# H-bridge.net
KiCad netlist of a schematic drawn in EAGLE
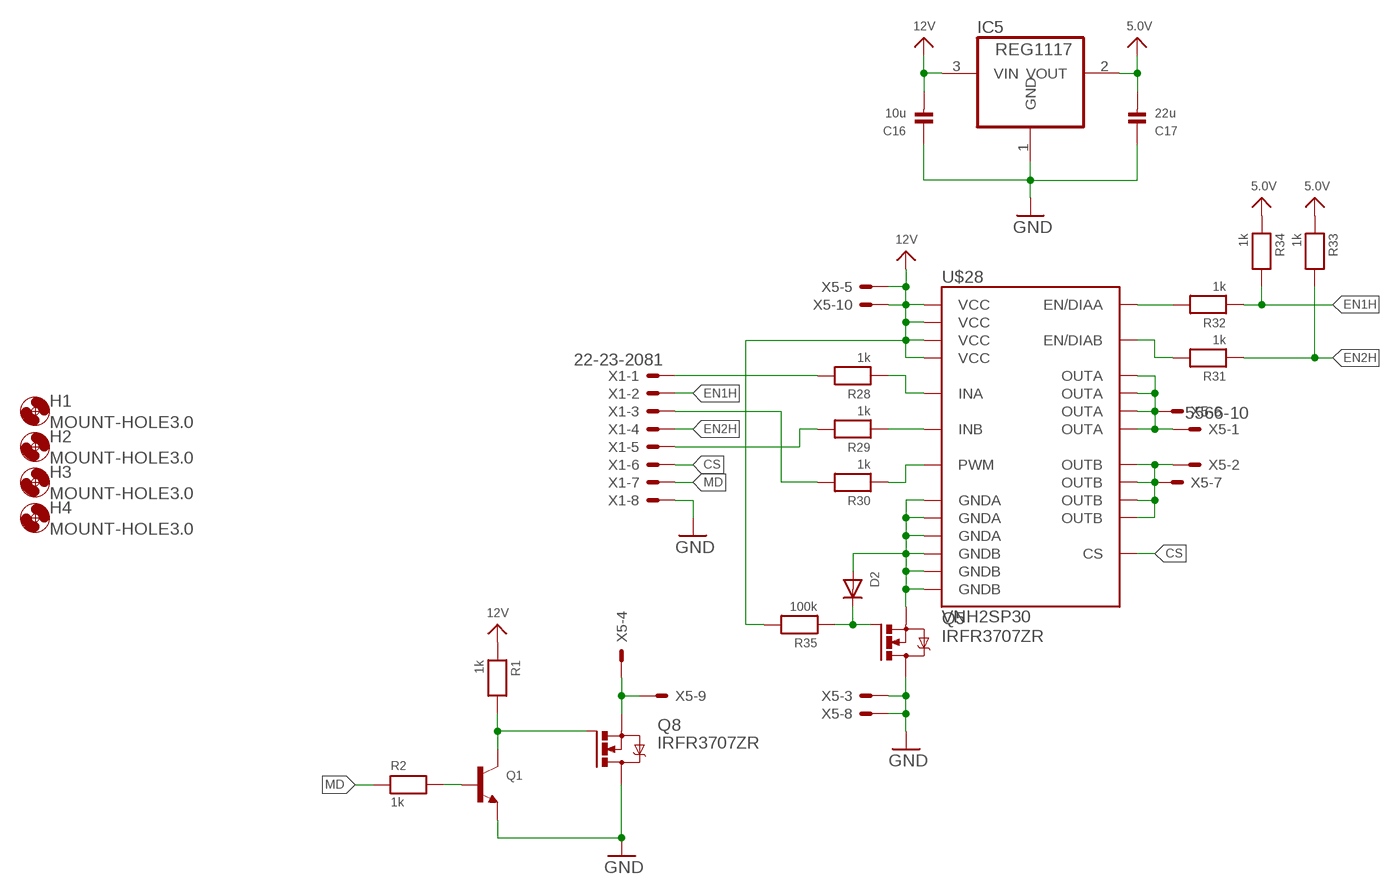
[diagram p0: schematic, sheet 1]

(export (version "E")
  (design (tool "Eeschema 10.0.6"))
  (components
    (comp (ref "C16")
      (value "10u")
      (footprint "eagle-import:_0805")
      (libsource (lib "eagle-import") (part "CAP_CERAMIC_0805"))
    )
    (comp (ref "C17")
      (value "22u")
      (footprint "eagle-import:_0805")
      (libsource (lib "eagle-import") (part "CAP_CERAMIC_0805"))
    )
    (comp (ref "D2")
      (value "DIODESMA")
      (footprint "eagle-import:SMADIODE")
      (libsource (lib "eagle-import") (part "DIODESMA"))
    )
    (comp (ref "H1")
      (value "MOUNT-HOLE3.0")
      (footprint "eagle-import:3,0")
      (libsource (lib "eagle-import") (part "MOUNT-HOLE3.0"))
    )
    (comp (ref "H2")
      (value "MOUNT-HOLE3.0")
      (footprint "eagle-import:3,0")
      (libsource (lib "eagle-import") (part "MOUNT-HOLE3.0"))
    )
    (comp (ref "H3")
      (value "MOUNT-HOLE3.0")
      (footprint "eagle-import:3,0")
      (libsource (lib "eagle-import") (part "MOUNT-HOLE3.0"))
    )
    (comp (ref "H4")
      (value "MOUNT-HOLE3.0")
      (footprint "eagle-import:3,0")
      (libsource (lib "eagle-import") (part "MOUNT-HOLE3.0"))
    )
    (comp (ref "IC5")
      (value "REG1117")
      (footprint "eagle-import:SOT223")
      (libsource (lib "eagle-import") (part "REG1117"))
    )
    (comp (ref "Q1")
      (value "TRANSISTOR_NPNWIDE")
      (footprint "eagle-import:SOT23-WIDE")
      (libsource (lib "eagle-import") (part "TRANSISTOR_NPNWIDE"))
    )
    (comp (ref "Q5")
      (value "IRFR3707ZR")
      (footprint "eagle-import:D-PAK_TO252AA")
      (libsource (lib "eagle-import") (part "IRFR3707ZR"))
    )
    (comp (ref "Q8")
      (value "IRFR3707ZR")
      (footprint "eagle-import:D-PAK_TO252AA")
      (libsource (lib "eagle-import") (part "IRFR3707ZR"))
    )
    (comp (ref "R1")
      (value "1k")
      (footprint "eagle-import:_0603")
      (libsource (lib "eagle-import") (part "RESISTOR_0603"))
    )
    (comp (ref "R2")
      (value "1k")
      (footprint "eagle-import:_0603")
      (libsource (lib "eagle-import") (part "RESISTOR_0603"))
    )
    (comp (ref "R28")
      (value "1k")
      (footprint "eagle-import:_0603")
      (libsource (lib "eagle-import") (part "RESISTOR_0603"))
    )
    (comp (ref "R29")
      (value "1k")
      (footprint "eagle-import:_0603")
      (libsource (lib "eagle-import") (part "RESISTOR_0603"))
    )
    (comp (ref "R30")
      (value "1k")
      (footprint "eagle-import:_0603")
      (libsource (lib "eagle-import") (part "RESISTOR_0603"))
    )
    (comp (ref "R31")
      (value "1k")
      (footprint "eagle-import:_0603")
      (libsource (lib "eagle-import") (part "RESISTOR_0603"))
    )
    (comp (ref "R32")
      (value "1k")
      (footprint "eagle-import:_0603")
      (libsource (lib "eagle-import") (part "RESISTOR_0603"))
    )
    (comp (ref "R33")
      (value "1k")
      (footprint "eagle-import:_0603")
      (libsource (lib "eagle-import") (part "RESISTOR_0603"))
    )
    (comp (ref "R34")
      (value "1k")
      (footprint "eagle-import:_0603")
      (libsource (lib "eagle-import") (part "RESISTOR_0603"))
    )
    (comp (ref "R35")
      (value "100k")
      (footprint "eagle-import:_0603")
      (libsource (lib "eagle-import") (part "RESISTOR_0603"))
    )
    (comp (ref "U$28")
      (value "VNH2SP30")
      (footprint "eagle-import:VNH2SP30")
      (libsource (lib "eagle-import") (part "VNH2SP30"))
    )
    (comp (ref "X1")
      (value "22-23-2081")
      (footprint "eagle-import:22-23-2081")
      (fields (field (name "MF") "MOLEX"))
      (libsource (lib "eagle-import") (part "22-23-2081"))
    )
    (comp (ref "X5")
      (value "5566-10")
      (footprint "eagle-import:5566-10")
      (libsource (lib "eagle-import") (part "5566-10"))
    )
  )
  (nets
    (net (code "1") (name "5.0V") (class "Default")
      (node (ref "C17") (pin "2") (pinfunction "P$2_2") (pintype "passive"))
      (node (ref "IC5") (pin "2") (pinfunction "VOUT_2") (pintype "output"))
      (node (ref "R33") (pin "1") (pinfunction "1_1") (pintype "passive"))
      (node (ref "R34") (pin "1") (pinfunction "1_1") (pintype "passive"))
    )
    (net (code "2") (name "12V") (class "Default")
      (node (ref "C16") (pin "2") (pinfunction "P$2_2") (pintype "passive"))
      (node (ref "IC5") (pin "3") (pinfunction "VIN_3") (pintype "input"))
      (node (ref "R1") (pin "1") (pinfunction "1_1") (pintype "passive"))
      (node (ref "R35") (pin "2") (pinfunction "2_2") (pintype "passive"))
      (node (ref "U$28") (pin "13") (pinfunction "VCC_13") (pintype "bidirectional"))
      (node (ref "U$28") (pin "23") (pinfunction "VCC_23") (pintype "bidirectional"))
      (node (ref "U$28") (pin "3") (pinfunction "VCC_3") (pintype "bidirectional"))
      (node (ref "U$28") (pin "SLUG1") (pinfunction "VCC_SLUG1") (pintype "bidirectional"))
      (node (ref "X5") (pin "10") (pinfunction "S_10") (pintype "passive"))
      (node (ref "X5") (pin "5") (pinfunction "S_5") (pintype "passive"))
    )
    (net (code "3") (name "CS") (class "Default")
      (node (ref "U$28") (pin "9") (pinfunction "CS_9") (pintype "bidirectional"))
      (node (ref "X1") (pin "6") (pinfunction "S_6") (pintype "passive"))
    )
    (net (code "4") (name "EN1H") (class "Default")
      (node (ref "R32") (pin "1") (pinfunction "1_1") (pintype "passive"))
      (node (ref "R34") (pin "2") (pinfunction "2_2") (pintype "passive"))
      (node (ref "X1") (pin "2") (pinfunction "S_2") (pintype "passive"))
    )
    (net (code "5") (name "EN2H") (class "Default")
      (node (ref "R31") (pin "1") (pinfunction "1_1") (pintype "passive"))
      (node (ref "R33") (pin "2") (pinfunction "2_2") (pintype "passive"))
      (node (ref "X1") (pin "4") (pinfunction "S_4") (pintype "passive"))
    )
    (net (code "6") (name "GND") (class "Default")
      (node (ref "C16") (pin "1") (pinfunction "P$1_1") (pintype "passive"))
      (node (ref "C17") (pin "1") (pinfunction "P$1_1") (pintype "passive"))
      (node (ref "IC5") (pin "1") (pinfunction "GND_1") (pintype "power_in"))
      (node (ref "Q1") (pin "2") (pinfunction "E_2") (pintype "passive"))
      (node (ref "Q5") (pin "4") (pinfunction "D_4") (pintype "passive"))
      (node (ref "Q8") (pin "4") (pinfunction "D_4") (pintype "passive"))
      (node (ref "X1") (pin "8") (pinfunction "S_8") (pintype "passive"))
      (node (ref "X5") (pin "3") (pinfunction "S_3") (pintype "passive"))
      (node (ref "X5") (pin "8") (pinfunction "S_8") (pintype "passive"))
    )
    (net (code "7") (name "MD") (class "Default")
      (node (ref "R2") (pin "1") (pinfunction "1_1") (pintype "passive"))
      (node (ref "X1") (pin "7") (pinfunction "S_7") (pintype "passive"))
    )
    (net (code "8") (name "Net-(Q1-B)") (class "Default")
      (node (ref "Q1") (pin "1") (pinfunction "B_1") (pintype "passive"))
      (node (ref "R2") (pin "2") (pinfunction "2_2") (pintype "passive"))
    )
    (net (code "9") (name "Net-(Q1-C)") (class "Default")
      (node (ref "Q1") (pin "3") (pinfunction "C_3") (pintype "passive"))
      (node (ref "Q8") (pin "1") (pinfunction "G_1") (pintype "passive"))
      (node (ref "R1") (pin "2") (pinfunction "2_2") (pintype "passive"))
    )
    (net (code "10") (name "Net-(Q5-G)") (class "Default")
      (node (ref "D2") (pin "C") (pinfunction "C_C") (pintype "passive"))
      (node (ref "Q5") (pin "1") (pinfunction "G_1") (pintype "passive"))
      (node (ref "R35") (pin "1") (pinfunction "1_1") (pintype "passive"))
    )
    (net (code "11") (name "Net-(Q5-S)") (class "Default")
      (node (ref "D2") (pin "A") (pinfunction "A_A") (pintype "passive"))
      (node (ref "Q5") (pin "3") (pinfunction "S_3") (pintype "passive"))
      (node (ref "U$28") (pin "18") (pinfunction "GNDB_18") (pintype "bidirectional"))
      (node (ref "U$28") (pin "19") (pinfunction "GNDB_19") (pintype "bidirectional"))
      (node (ref "U$28") (pin "20") (pinfunction "GNDB_20") (pintype "bidirectional"))
      (node (ref "U$28") (pin "26") (pinfunction "GNDA_26") (pintype "bidirectional"))
      (node (ref "U$28") (pin "27") (pinfunction "GNDA_27") (pintype "bidirectional"))
      (node (ref "U$28") (pin "28") (pinfunction "GNDA_28") (pintype "bidirectional"))
    )
    (net (code "12") (name "Net-(Q8-S)") (class "Default")
      (node (ref "Q8") (pin "3") (pinfunction "S_3") (pintype "passive"))
      (node (ref "X5") (pin "4") (pinfunction "S_4") (pintype "passive"))
      (node (ref "X5") (pin "9") (pinfunction "S_9") (pintype "passive"))
    )
    (net (code "13") (name "Net-(U$28-EN{slash}DIAA)") (class "Default")
      (node (ref "R32") (pin "2") (pinfunction "2_2") (pintype "passive"))
      (node (ref "U$28") (pin "6") (pinfunction "EN/DIAA_6") (pintype "bidirectional"))
    )
    (net (code "14") (name "Net-(U$28-EN{slash}DIAB)") (class "Default")
      (node (ref "R31") (pin "2") (pinfunction "2_2") (pintype "passive"))
      (node (ref "U$28") (pin "10") (pinfunction "EN/DIAB_10") (pintype "bidirectional"))
    )
    (net (code "15") (name "Net-(U$28-INA)") (class "Default")
      (node (ref "R28") (pin "1") (pinfunction "1_1") (pintype "passive"))
      (node (ref "U$28") (pin "5") (pinfunction "INA_5") (pintype "bidirectional"))
    )
    (net (code "16") (name "Net-(U$28-INB)") (class "Default")
      (node (ref "R29") (pin "1") (pinfunction "1_1") (pintype "passive"))
      (node (ref "U$28") (pin "11") (pinfunction "INB_11") (pintype "bidirectional"))
    )
    (net (code "17") (name "Net-(U$28-PWM)") (class "Default")
      (node (ref "R30") (pin "1") (pinfunction "1_1") (pintype "passive"))
      (node (ref "U$28") (pin "8") (pinfunction "PWM_8") (pintype "bidirectional"))
    )
    (net (code "18") (name "Net-(X1A-S)") (class "Default")
      (node (ref "R28") (pin "2") (pinfunction "2_2") (pintype "passive"))
      (node (ref "X1") (pin "1") (pinfunction "S_1") (pintype "passive"))
    )
    (net (code "19") (name "Net-(X1C-S)") (class "Default")
      (node (ref "R30") (pin "2") (pinfunction "2_2") (pintype "passive"))
      (node (ref "X1") (pin "3") (pinfunction "S_3") (pintype "passive"))
    )
    (net (code "20") (name "Net-(X1E-S)") (class "Default")
      (node (ref "R29") (pin "2") (pinfunction "2_2") (pintype "passive"))
      (node (ref "X1") (pin "5") (pinfunction "S_5") (pintype "passive"))
    )
    (net (code "21") (name "Net-(X5A-S)") (class "Default")
      (node (ref "U$28") (pin "1") (pinfunction "OUTA_1") (pintype "bidirectional"))
      (node (ref "U$28") (pin "25") (pinfunction "OUTA_25") (pintype "bidirectional"))
      (node (ref "U$28") (pin "30") (pinfunction "OUTA_30") (pintype "bidirectional"))
      (node (ref "U$28") (pin "SLUG3") (pinfunction "OUTA_SLUG3") (pintype "bidirectional"))
      (node (ref "X5") (pin "1") (pinfunction "S_1") (pintype "passive"))
      (node (ref "X5") (pin "6") (pinfunction "S_6") (pintype "passive"))
    )
    (net (code "22") (name "Net-(X5C-S)") (class "Default")
      (node (ref "U$28") (pin "15") (pinfunction "OUTB_15") (pintype "bidirectional"))
      (node (ref "U$28") (pin "16") (pinfunction "OUTB_16") (pintype "bidirectional"))
      (node (ref "U$28") (pin "21") (pinfunction "OUTB_21") (pintype "bidirectional"))
      (node (ref "U$28") (pin "SLUG2") (pinfunction "OUTB_SLUG2") (pintype "bidirectional"))
      (node (ref "X5") (pin "2") (pinfunction "S_2") (pintype "passive"))
      (node (ref "X5") (pin "7") (pinfunction "S_7") (pintype "passive"))
    )
  )
)
